# pipower.net
KiCad netlist of a schematic drawn in EAGLE
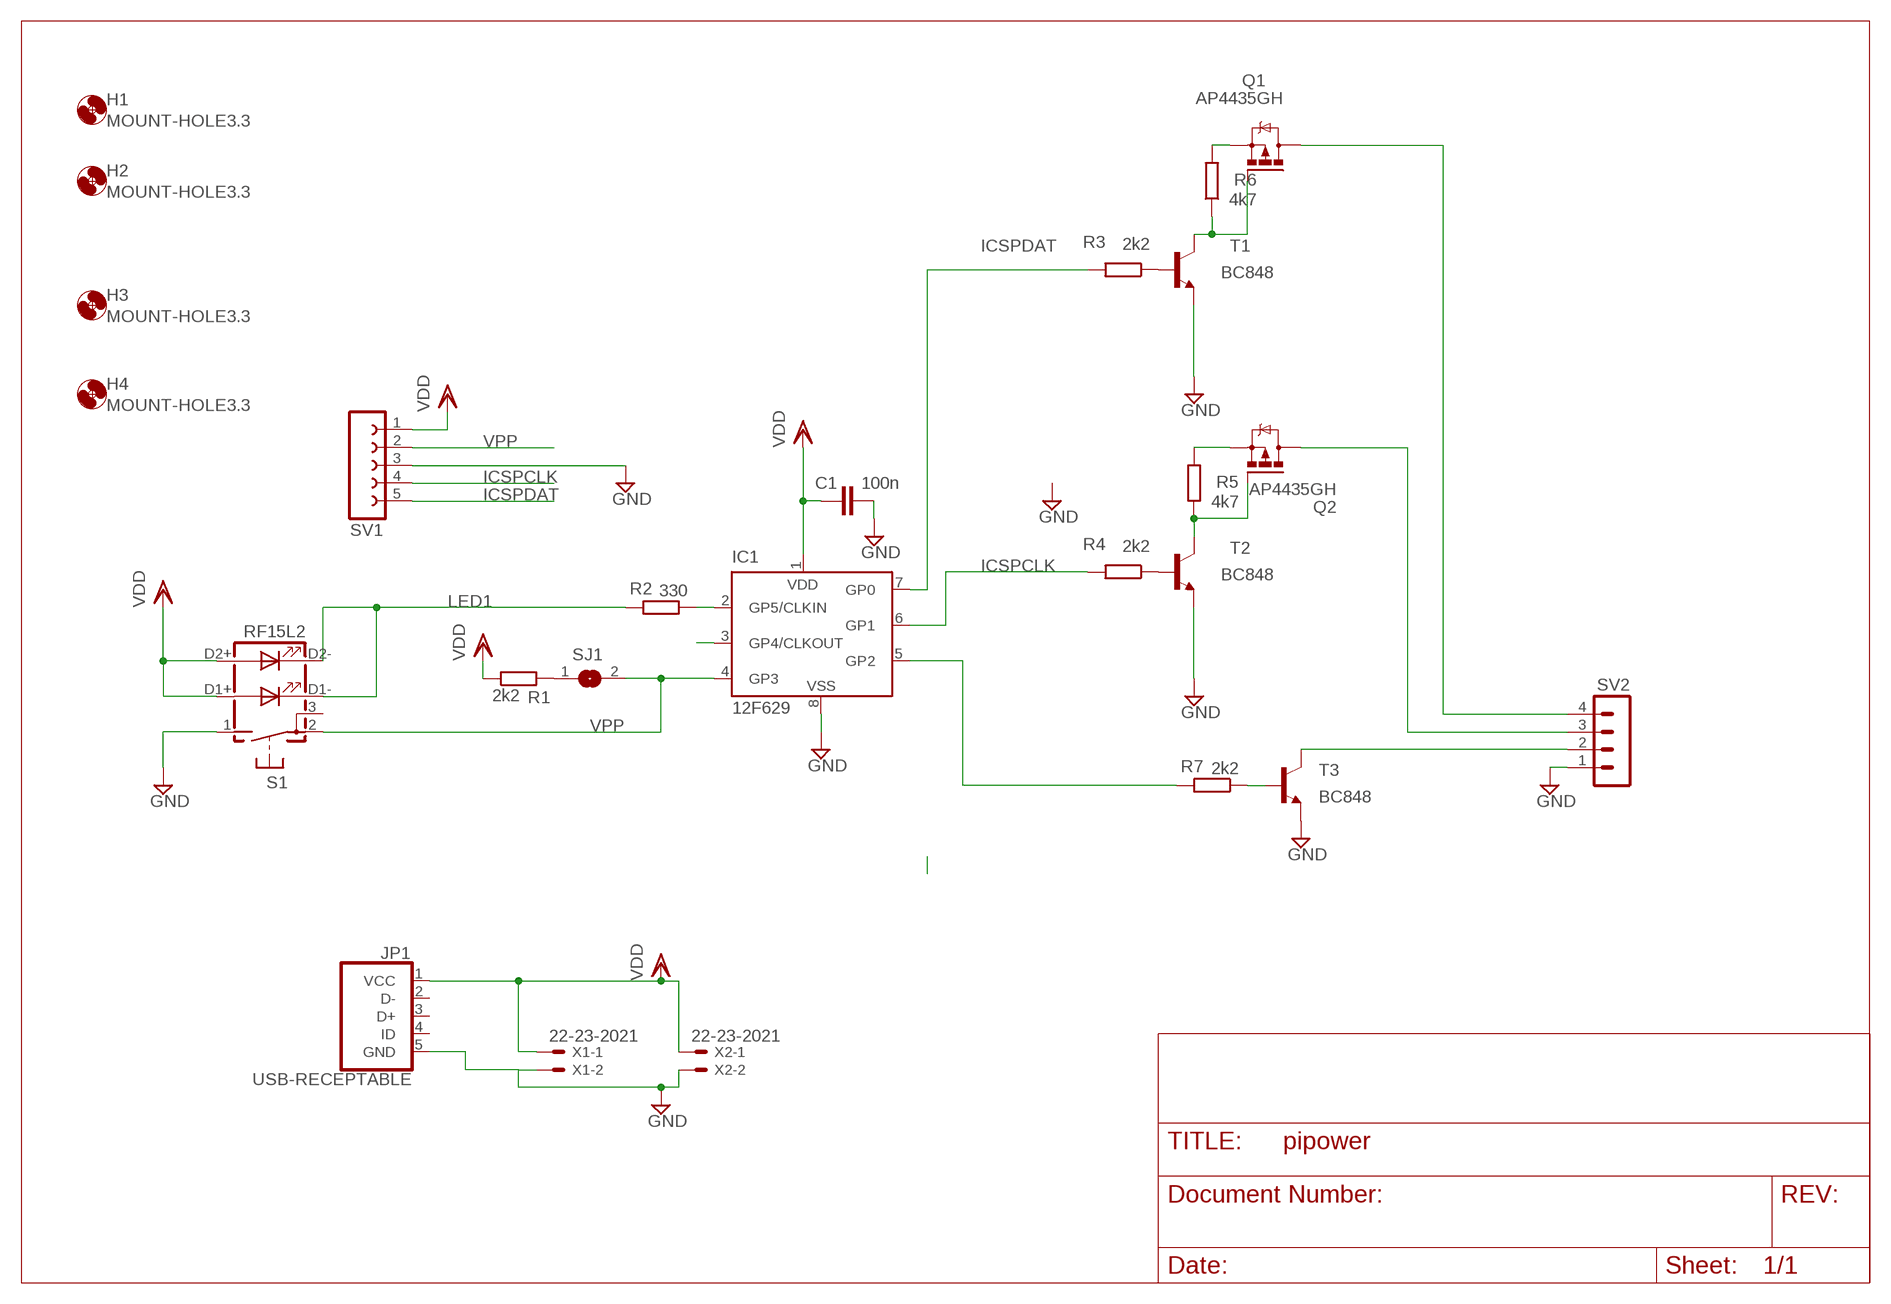
[diagram p0: schematic, sheet 1]

(export (version "E")
  (design (tool "Eeschema 10.0.6"))
  (components
    (comp (ref "C1")
      (value "100n")
      (footprint "eagle-import:C0805")
      (libsource (lib "eagle-import") (part "C-EUC0805"))
    )
    (comp (ref "H1")
      (value "MOUNT-HOLE3.3")
      (footprint "eagle-import:3,3")
      (libsource (lib "eagle-import") (part "MOUNT-HOLE3.3"))
    )
    (comp (ref "H2")
      (value "MOUNT-HOLE3.3")
      (footprint "eagle-import:3,3")
      (libsource (lib "eagle-import") (part "MOUNT-HOLE3.3"))
    )
    (comp (ref "H3")
      (value "MOUNT-HOLE3.3")
      (footprint "eagle-import:3,3")
      (libsource (lib "eagle-import") (part "MOUNT-HOLE3.3"))
    )
    (comp (ref "H4")
      (value "MOUNT-HOLE3.3")
      (footprint "eagle-import:3,3")
      (libsource (lib "eagle-import") (part "MOUNT-HOLE3.3"))
    )
    (comp (ref "IC1")
      (value "12F629")
      (footprint "eagle-import:SO-08")
      (fields
        (field (name "MF") "MICROCHIP")
        (field (name "MPN") "PIC12F629-I/SN")
        (field (name "MPN_1") "PIC12F629-I/SN")
        (field (name "OC_FARNELL") "9759000")
        (field (name "OC_NEWARK") "61K3433")
      )
      (libsource (lib "eagle-import") (part "PIC12F6SN29"))
    )
    (comp (ref "JP1")
      (value "USB-RECEPTABLE")
      (footprint "eagle-import:FCI-10103594-0001LF")
      (libsource (lib "eagle-import") (part "USB-RECEPTABLE"))
    )
    (comp (ref "Q1")
      (value "AP4435GH")
      (footprint "eagle-import:D-PAK_TO252AA")
      (libsource (lib "eagle-import") (part "IRF?5305R"))
    )
    (comp (ref "Q2")
      (value "AP4435GH")
      (footprint "eagle-import:D-PAK_TO252AA")
      (libsource (lib "eagle-import") (part "IRF?5305R"))
    )
    (comp (ref "R1")
      (value "2k2")
      (footprint "eagle-import:R0805")
      (libsource (lib "eagle-import") (part "R-EU_R0805"))
    )
    (comp (ref "R2")
      (value "330")
      (footprint "eagle-import:R0805")
      (libsource (lib "eagle-import") (part "R-EU_R0805"))
    )
    (comp (ref "R3")
      (value "2k2")
      (footprint "eagle-import:R0805")
      (libsource (lib "eagle-import") (part "R-EU_R0805"))
    )
    (comp (ref "R4")
      (value "2k2")
      (footprint "eagle-import:R0805")
      (libsource (lib "eagle-import") (part "R-EU_R0805"))
    )
    (comp (ref "R5")
      (value "4k7")
      (footprint "eagle-import:R0805")
      (libsource (lib "eagle-import") (part "R-EU_R0805"))
    )
    (comp (ref "R6")
      (value "4k7")
      (footprint "eagle-import:R0805")
      (libsource (lib "eagle-import") (part "R-EU_R0805"))
    )
    (comp (ref "R7")
      (value "2k2")
      (footprint "eagle-import:R0805")
      (libsource (lib "eagle-import") (part "R-EU_R0805"))
    )
    (comp (ref "S1")
      (value "RF15L2")
      (footprint "eagle-import:RF15L2")
      (libsource (lib "eagle-import") (part "RF15L2"))
    )
    (comp (ref "SJ1") (value "SJ") (footprint "eagle-import:SJ") (libsource (lib "eagle-import") (part "SJ")))
    (comp (ref "SV1")
      (value "FE05-1")
      (footprint "eagle-import:FE05-1")
      (libsource (lib "eagle-import") (part "FE05-1"))
    )
    (comp (ref "SV2")
      (value "MA04-1")
      (footprint "eagle-import:MA04-1")
      (libsource (lib "eagle-import") (part "MA04-1"))
    )
    (comp (ref "T1")
      (value "BC848")
      (footprint "eagle-import:SOT23")
      (libsource (lib "eagle-import") (part "BC848"))
    )
    (comp (ref "T2")
      (value "BC848")
      (footprint "eagle-import:SOT23")
      (libsource (lib "eagle-import") (part "BC848"))
    )
    (comp (ref "T3")
      (value "BC848")
      (footprint "eagle-import:SOT23")
      (libsource (lib "eagle-import") (part "BC848"))
    )
    (comp (ref "X1")
      (value "22-23-2021")
      (footprint "eagle-import:22-23-2021")
      (fields (field (name "MF") "MOLEX"))
      (libsource (lib "eagle-import") (part "22-23-2021"))
    )
    (comp (ref "X2")
      (value "22-23-2021")
      (footprint "eagle-import:22-23-2021")
      (fields (field (name "MF") "MOLEX"))
      (libsource (lib "eagle-import") (part "22-23-2021"))
    )
  )
  (nets
    (net (code "1") (name "/ICSPCLK") (class "Default")
      (node (ref "IC1") (pin "6") (pinfunction "GP1_6") (pintype "bidirectional"))
      (node (ref "R4") (pin "2") (pinfunction "2_2") (pintype "passive"))
      (node (ref "SV1") (pin "4") (pinfunction "4_4") (pintype "passive"))
    )
    (net (code "2") (name "/ICSPDAT") (class "Default")
      (node (ref "IC1") (pin "7") (pinfunction "GP0_7") (pintype "bidirectional"))
      (node (ref "R3") (pin "2") (pinfunction "2_2") (pintype "passive"))
      (node (ref "SV1") (pin "5") (pinfunction "5_5") (pintype "passive"))
    )
    (net (code "3") (name "/LED1") (class "Default")
      (node (ref "R2") (pin "2") (pinfunction "2_2") (pintype "passive"))
      (node (ref "S1") (pin "D1-") (pinfunction "C1_D1-") (pintype "passive"))
      (node (ref "S1") (pin "D2-") (pinfunction "C2_D2-") (pintype "passive"))
    )
    (net (code "4") (name "/VPP") (class "Default")
      (node (ref "IC1") (pin "4") (pinfunction "GP3_4") (pintype "input"))
      (node (ref "S1") (pin "2") (pinfunction "P_2") (pintype "passive"))
      (node (ref "SJ1") (pin "2") (pinfunction "2_2") (pintype "passive"))
      (node (ref "SV1") (pin "2") (pinfunction "2_2") (pintype "passive"))
    )
    (net (code "5") (name "GND") (class "Default")
      (node (ref "C1") (pin "2") (pinfunction "2_2") (pintype "passive"))
      (node (ref "IC1") (pin "8") (pinfunction "VSS_8") (pintype "power_in"))
      (node (ref "JP1") (pin "5") (pinfunction "GND_5") (pintype "bidirectional"))
      (node (ref "S1") (pin "1") (pinfunction "S_1") (pintype "passive"))
      (node (ref "SV1") (pin "3") (pinfunction "3_3") (pintype "passive"))
      (node (ref "SV2") (pin "1") (pinfunction "1_1") (pintype "passive"))
      (node (ref "T1") (pin "2") (pinfunction "E_2") (pintype "passive"))
      (node (ref "T2") (pin "2") (pinfunction "E_2") (pintype "passive"))
      (node (ref "T3") (pin "2") (pinfunction "E_2") (pintype "passive"))
      (node (ref "X1") (pin "2") (pinfunction "S_2") (pintype "passive"))
      (node (ref "X2") (pin "2") (pinfunction "S_2") (pintype "passive"))
    )
    (net (code "6") (name "Net-(IC1-GP2)") (class "Default")
      (node (ref "IC1") (pin "5") (pinfunction "GP2_5") (pintype "bidirectional"))
      (node (ref "R7") (pin "2") (pinfunction "2_2") (pintype "passive"))
    )
    (net (code "7") (name "Net-(IC1-GP5{slash}CLKIN)") (class "Default")
      (node (ref "IC1") (pin "2") (pinfunction "GP5/CLKIN_2") (pintype "bidirectional"))
      (node (ref "R2") (pin "1") (pinfunction "1_1") (pintype "passive"))
    )
    (net (code "8") (name "Net-(Q1-D)") (class "Default")
      (node (ref "Q1") (pin "4") (pinfunction "D_4") (pintype "passive"))
      (node (ref "SV2") (pin "4") (pinfunction "4_4") (pintype "passive"))
    )
    (net (code "9") (name "Net-(Q1-G)") (class "Default")
      (node (ref "Q1") (pin "1") (pinfunction "G_1") (pintype "passive"))
      (node (ref "R6") (pin "1") (pinfunction "1_1") (pintype "passive"))
      (node (ref "T1") (pin "3") (pinfunction "C_3") (pintype "passive"))
    )
    (net (code "10") (name "Net-(Q1-S)") (class "Default")
      (node (ref "Q1") (pin "3") (pinfunction "S_3") (pintype "passive"))
      (node (ref "R6") (pin "2") (pinfunction "2_2") (pintype "passive"))
    )
    (net (code "11") (name "Net-(Q2-D)") (class "Default")
      (node (ref "Q2") (pin "4") (pinfunction "D_4") (pintype "passive"))
      (node (ref "SV2") (pin "3") (pinfunction "3_3") (pintype "passive"))
    )
    (net (code "12") (name "Net-(Q2-G)") (class "Default")
      (node (ref "Q2") (pin "1") (pinfunction "G_1") (pintype "passive"))
      (node (ref "R5") (pin "1") (pinfunction "1_1") (pintype "passive"))
      (node (ref "T2") (pin "3") (pinfunction "C_3") (pintype "passive"))
    )
    (net (code "13") (name "Net-(Q2-S)") (class "Default")
      (node (ref "Q2") (pin "3") (pinfunction "S_3") (pintype "passive"))
      (node (ref "R5") (pin "2") (pinfunction "2_2") (pintype "passive"))
    )
    (net (code "14") (name "Net-(R1-Pad2)") (class "Default")
      (node (ref "R1") (pin "2") (pinfunction "2_2") (pintype "passive"))
      (node (ref "SJ1") (pin "1") (pinfunction "1_1") (pintype "passive"))
    )
    (net (code "15") (name "Net-(T1-B)") (class "Default")
      (node (ref "R3") (pin "1") (pinfunction "1_1") (pintype "passive"))
      (node (ref "T1") (pin "1") (pinfunction "B_1") (pintype "passive"))
    )
    (net (code "16") (name "Net-(T2-B)") (class "Default")
      (node (ref "R4") (pin "1") (pinfunction "1_1") (pintype "passive"))
      (node (ref "T2") (pin "1") (pinfunction "B_1") (pintype "passive"))
    )
    (net (code "17") (name "Net-(T3-B)") (class "Default")
      (node (ref "R7") (pin "1") (pinfunction "1_1") (pintype "passive"))
      (node (ref "T3") (pin "1") (pinfunction "B_1") (pintype "passive"))
    )
    (net (code "18") (name "Net-(T3-C)") (class "Default")
      (node (ref "SV2") (pin "2") (pinfunction "2_2") (pintype "passive"))
      (node (ref "T3") (pin "3") (pinfunction "C_3") (pintype "passive"))
    )
    (net (code "19") (name "VDD") (class "Default")
      (node (ref "C1") (pin "1") (pinfunction "1_1") (pintype "passive"))
      (node (ref "IC1") (pin "1") (pinfunction "VDD_1") (pintype "power_in"))
      (node (ref "JP1") (pin "1") (pinfunction "VCC_1") (pintype "bidirectional"))
      (node (ref "R1") (pin "1") (pinfunction "1_1") (pintype "passive"))
      (node (ref "S1") (pin "D1+") (pinfunction "A1_D1+") (pintype "passive"))
      (node (ref "S1") (pin "D2+") (pinfunction "A2_D2+") (pintype "passive"))
      (node (ref "SV1") (pin "1") (pinfunction "1_1") (pintype "passive"))
      (node (ref "X1") (pin "1") (pinfunction "S_1") (pintype "passive"))
      (node (ref "X2") (pin "1") (pinfunction "S_1") (pintype "passive"))
    )
    (net (code "20") (name "unconnected-(IC1-GP4{slash}CLKOUT-Pad3)") (class "Default")
      (node (ref "IC1") (pin "3") (pinfunction "GP4/CLKOUT_3") (pintype "bidirectional"))
    )
    (net (code "21") (name "unconnected-(JP1-D+-Pad3)") (class "Default")
      (node (ref "JP1") (pin "3") (pinfunction "D+_3") (pintype "bidirectional"))
    )
    (net (code "22") (name "unconnected-(JP1-D--Pad2)") (class "Default")
      (node (ref "JP1") (pin "2") (pinfunction "D-_2") (pintype "bidirectional"))
    )
    (net (code "23") (name "unconnected-(JP1-ID-Pad4)") (class "Default")
      (node (ref "JP1") (pin "4") (pinfunction "ID_4") (pintype "bidirectional"))
    )
    (net (code "24") (name "unconnected-(S1-P-Pad3)") (class "Default")
      (node (ref "S1") (pin "3") (pinfunction "P_3") (pintype "passive"))
    )
  )
)
